# 05_-_QSPI_SD-CARD.net
KiCad netlist of a schematic drawn in Altium Designer
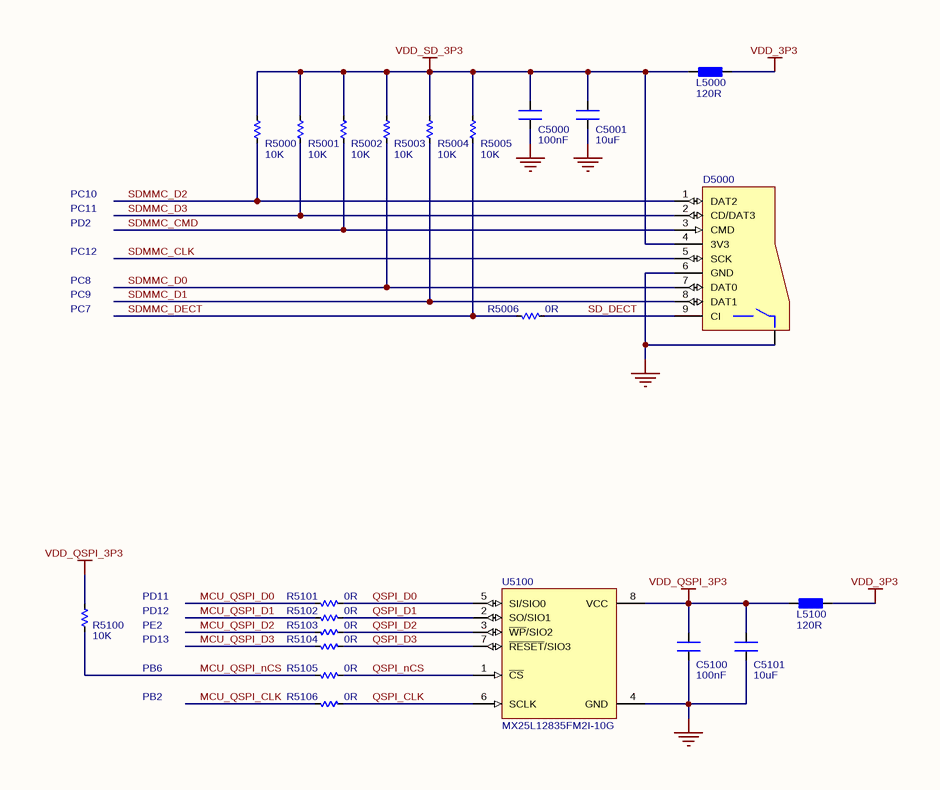
[diagram p0: 05 - QSPI & SD-CARD.SchDoc]

(export (version "E")
  (design (tool "Eeschema 10.0.6"))
  (components
    (comp (ref "C5000")
      (value "100nF")
      (footprint "CN-SMD-0402")
      (description "Ceramic Capacitor SMD 0402 100nF ±20% 16V")
      (fields (field (name "Comment") "Capacitor"))
      (libsource (lib "AS50") (part "Cap"))
    )
    (comp (ref "C5001")
      (value "10uF")
      (footprint "CN-SMD-0603")
      (description "Ceramic Capacitor SMD 0603 10uF ±20% 10V")
      (fields (field (name "Comment") "Capacitor"))
      (libsource (lib "AS50") (part "Cap"))
    )
    (comp (ref "C5100")
      (value "100nF")
      (footprint "CN-SMD-0402")
      (description "Ceramic Capacitor SMD 0402 100nF ±20% 16V")
      (fields (field (name "Comment") "Capacitor"))
      (libsource (lib "AS50") (part "Cap"))
    )
    (comp (ref "C5101")
      (value "10uF")
      (footprint "CN-SMD-0603")
      (description "Ceramic Capacitor SMD 0603 10uF ±20% 10V")
      (fields (field (name "Comment") "Capacitor"))
      (libsource (lib "AS50") (part "Cap"))
    )
    (comp (ref "D5000")
      (value "microSD card socket")
      (footprint "MICROSD1")
      (libsource (lib "AS50") (part "microSD card SDIO"))
    )
    (comp (ref "L5000")
      (value "120R")
      (footprint "L-SMD-0402")
      (description "Ferrite bead SMD 0402 120 Ohm @100MHz")
      (fields (field (name "Comment") "Ferrite bead"))
      (libsource (lib "AS50") (part "Ferrite bead"))
    )
    (comp (ref "L5100")
      (value "120R")
      (footprint "L-SMD-0402")
      (description "Ferrite bead SMD 0402 120 Ohm @100MHz")
      (fields (field (name "Comment") "Ferrite bead"))
      (libsource (lib "AS50") (part "Ferrite bead"))
    )
    (comp (ref "R5000")
      (value "10K")
      (footprint "RES-SMD-0402")
      (description "Resistor SMD 0402 10K 1% 0.063W")
      (fields (field (name "Comment") "Resistor"))
      (libsource (lib "AS50") (part "Res"))
    )
    (comp (ref "R5001")
      (value "10K")
      (footprint "RES-SMD-0402")
      (description "Resistor SMD 0402 10K 1% 0.063W")
      (fields (field (name "Comment") "Resistor"))
      (libsource (lib "AS50") (part "Res"))
    )
    (comp (ref "R5002")
      (value "10K")
      (footprint "RES-SMD-0402")
      (description "Resistor SMD 0402 10K 1% 0.063W")
      (fields (field (name "Comment") "Resistor"))
      (libsource (lib "AS50") (part "Res"))
    )
    (comp (ref "R5003")
      (value "10K")
      (footprint "RES-SMD-0402")
      (description "Resistor SMD 0402 10K 1% 0.063W")
      (fields (field (name "Comment") "Resistor"))
      (libsource (lib "AS50") (part "Res"))
    )
    (comp (ref "R5004")
      (value "10K")
      (footprint "RES-SMD-0402")
      (description "Resistor SMD 0402 10K 1% 0.063W")
      (fields (field (name "Comment") "Resistor"))
      (libsource (lib "AS50") (part "Res"))
    )
    (comp (ref "R5005")
      (value "10K")
      (footprint "RES-SMD-0402")
      (description "Resistor SMD 0402 10K 1% 0.063W")
      (fields (field (name "Comment") "Resistor"))
      (libsource (lib "AS50") (part "Res"))
    )
    (comp (ref "R5006")
      (value "0R")
      (footprint "RES-SMD-0402")
      (description "Resistor SMD 0402 0R 1% 0.063W")
      (fields (field (name "Comment") "Resistor"))
      (libsource (lib "AS50") (part "Res"))
    )
    (comp (ref "R5100")
      (value "10K")
      (footprint "RES-SMD-0402")
      (description "Resistor SMD 0402 10K 1% 0.063W")
      (fields (field (name "Comment") "Resistor"))
      (libsource (lib "AS50") (part "Res"))
    )
    (comp (ref "R5101")
      (value "0R")
      (footprint "RES-SMD-0402")
      (description "Resistor SMD 0402 0R 1% 0.063W")
      (fields (field (name "Comment") "Resistor"))
      (libsource (lib "AS50") (part "Res"))
    )
    (comp (ref "R5102")
      (value "0R")
      (footprint "RES-SMD-0402")
      (description "Resistor SMD 0402 0R 1% 0.063W")
      (fields (field (name "Comment") "Resistor"))
      (libsource (lib "AS50") (part "Res"))
    )
    (comp (ref "R5103")
      (value "0R")
      (footprint "RES-SMD-0402")
      (description "Resistor SMD 0402 0R 1% 0.063W")
      (fields (field (name "Comment") "Resistor"))
      (libsource (lib "AS50") (part "Res"))
    )
    (comp (ref "R5104")
      (value "0R")
      (footprint "RES-SMD-0402")
      (description "Resistor SMD 0402 0R 1% 0.063W")
      (fields (field (name "Comment") "Resistor"))
      (libsource (lib "AS50") (part "Res"))
    )
    (comp (ref "R5105")
      (value "0R")
      (footprint "RES-SMD-0402")
      (description "Resistor SMD 0402 0R 1% 0.063W")
      (fields (field (name "Comment") "Resistor"))
      (libsource (lib "AS50") (part "Res"))
    )
    (comp (ref "R5106")
      (value "0R")
      (footprint "RES-SMD-0402")
      (description "Resistor SMD 0402 0R 1% 0.063W")
      (fields (field (name "Comment") "Resistor"))
      (libsource (lib "AS50") (part "Res"))
    )
    (comp (ref "U5100")
      (value "MX25L12835FM2I-10G")
      (footprint "SOIC127P798X216-8N")
      (description "Macronix 3V, 128M-BIT [x1/x2/x4] CMOS MXSMIO® (Serial Multi I/O) Flash Memory")
      (libsource (lib "AS50") (part "MX25L12835FM2I-10G"))
    )
  )
  (nets
    (net (code "1") (name "/MCU_QSPI_CLK") (class "Default")
      (node (ref "R5106") (pin "2") (pinfunction "2_2") (pintype "passive"))
    )
    (net (code "2") (name "/MCU_QSPI_D0") (class "Default")
      (node (ref "R5101") (pin "2") (pinfunction "2_2") (pintype "passive"))
    )
    (net (code "3") (name "/MCU_QSPI_D1") (class "Default")
      (node (ref "R5102") (pin "2") (pinfunction "2_2") (pintype "passive"))
    )
    (net (code "4") (name "/MCU_QSPI_D2") (class "Default")
      (node (ref "R5103") (pin "2") (pinfunction "2_2") (pintype "passive"))
    )
    (net (code "5") (name "/MCU_QSPI_D3") (class "Default")
      (node (ref "R5104") (pin "2") (pinfunction "2_2") (pintype "passive"))
    )
    (net (code "6") (name "/MCU_QSPI_nCS") (class "Default")
      (node (ref "R5100") (pin "2") (pinfunction "2_2") (pintype "passive"))
      (node (ref "R5105") (pin "2") (pinfunction "2_2") (pintype "passive"))
    )
    (net (code "7") (name "/QSPI_CLK") (class "Default")
      (node (ref "R5106") (pin "1") (pinfunction "1_1") (pintype "passive"))
      (node (ref "U5100") (pin "6") (pinfunction "SCLK_6") (pintype "input"))
    )
    (net (code "8") (name "/QSPI_D0") (class "Default")
      (node (ref "R5101") (pin "1") (pinfunction "1_1") (pintype "passive"))
      (node (ref "U5100") (pin "5") (pinfunction "SI/SIO0_5") (pintype "bidirectional"))
    )
    (net (code "9") (name "/QSPI_D1") (class "Default")
      (node (ref "R5102") (pin "1") (pinfunction "1_1") (pintype "passive"))
      (node (ref "U5100") (pin "2") (pinfunction "SO/SIO1_2") (pintype "bidirectional"))
    )
    (net (code "10") (name "/QSPI_D2") (class "Default")
      (node (ref "R5103") (pin "1") (pinfunction "1_1") (pintype "passive"))
      (node (ref "U5100") (pin "3") (pinfunction "~{WP}/SIO2_3") (pintype "bidirectional"))
    )
    (net (code "11") (name "/QSPI_D3") (class "Default")
      (node (ref "R5104") (pin "1") (pinfunction "1_1") (pintype "passive"))
      (node (ref "U5100") (pin "7") (pinfunction "~{RESET}/SIO3_7") (pintype "bidirectional"))
    )
    (net (code "12") (name "/QSPI_nCS") (class "Default")
      (node (ref "R5105") (pin "1") (pinfunction "1_1") (pintype "passive"))
      (node (ref "U5100") (pin "1") (pinfunction "~{CS}_1") (pintype "input"))
    )
    (net (code "13") (name "/SDMMC_CLK") (class "Default")
      (node (ref "D5000") (pin "5") (pinfunction "SCK_5") (pintype "bidirectional"))
    )
    (net (code "14") (name "/SDMMC_CMD") (class "Default")
      (node (ref "D5000") (pin "3") (pinfunction "CMD_3") (pintype "input"))
      (node (ref "R5002") (pin "2") (pinfunction "2_2") (pintype "passive"))
    )
    (net (code "15") (name "/SDMMC_D0") (class "Default")
      (node (ref "D5000") (pin "7") (pinfunction "DAT0_7") (pintype "bidirectional"))
      (node (ref "R5003") (pin "2") (pinfunction "2_2") (pintype "passive"))
    )
    (net (code "16") (name "/SDMMC_D1") (class "Default")
      (node (ref "D5000") (pin "8") (pinfunction "DAT1_8") (pintype "bidirectional"))
      (node (ref "R5004") (pin "2") (pinfunction "2_2") (pintype "passive"))
    )
    (net (code "17") (name "/SDMMC_D2") (class "Default")
      (node (ref "D5000") (pin "1") (pinfunction "DAT2_1") (pintype "bidirectional"))
      (node (ref "R5000") (pin "2") (pinfunction "2_2") (pintype "passive"))
    )
    (net (code "18") (name "/SDMMC_D3") (class "Default")
      (node (ref "D5000") (pin "2") (pinfunction "CD/DAT3_2") (pintype "bidirectional"))
      (node (ref "R5001") (pin "2") (pinfunction "2_2") (pintype "passive"))
    )
    (net (code "19") (name "/SDMMC_DECT") (class "Default")
      (node (ref "R5005") (pin "2") (pinfunction "2_2") (pintype "passive"))
      (node (ref "R5006") (pin "2") (pinfunction "2_2") (pintype "passive"))
    )
    (net (code "20") (name "/SD_DECT") (class "Default")
      (node (ref "D5000") (pin "9") (pinfunction "CI_9") (pintype "passive"))
      (node (ref "R5006") (pin "1") (pinfunction "1_1") (pintype "passive"))
    )
    (net (code "21") (name "GND") (class "Default")
      (node (ref "C5000") (pin "1") (pinfunction "1_1") (pintype "passive"))
      (node (ref "C5001") (pin "1") (pinfunction "1_1") (pintype "passive"))
      (node (ref "C5100") (pin "1") (pinfunction "1_1") (pintype "passive"))
      (node (ref "C5101") (pin "1") (pinfunction "1_1") (pintype "passive"))
      (node (ref "D5000") (pin "0") (pinfunction "NC_0") (pintype "passive"))
      (node (ref "D5000") (pin "6") (pinfunction "GND_6") (pintype "power_in"))
      (node (ref "U5100") (pin "4") (pinfunction "GND_4") (pintype "power_in"))
    )
    (net (code "22") (name "VDD_3P3") (class "Default")
      (node (ref "L5000") (pin "1") (pinfunction "1_1") (pintype "passive"))
      (node (ref "L5100") (pin "1") (pinfunction "1_1") (pintype "passive"))
    )
    (net (code "23") (name "VDD_QSPI_3P3") (class "Default")
      (node (ref "C5100") (pin "2") (pinfunction "2_2") (pintype "passive"))
      (node (ref "C5101") (pin "2") (pinfunction "2_2") (pintype "passive"))
      (node (ref "L5100") (pin "2") (pinfunction "2_2") (pintype "passive"))
      (node (ref "R5100") (pin "1") (pinfunction "1_1") (pintype "passive"))
      (node (ref "U5100") (pin "8") (pinfunction "VCC_8") (pintype "power_in"))
    )
    (net (code "24") (name "VDD_SD_3P3") (class "Default")
      (node (ref "C5000") (pin "2") (pinfunction "2_2") (pintype "passive"))
      (node (ref "C5001") (pin "2") (pinfunction "2_2") (pintype "passive"))
      (node (ref "D5000") (pin "4") (pinfunction "3V3_4") (pintype "power_in"))
      (node (ref "L5000") (pin "2") (pinfunction "2_2") (pintype "passive"))
      (node (ref "R5000") (pin "1") (pinfunction "1_1") (pintype "passive"))
      (node (ref "R5001") (pin "1") (pinfunction "1_1") (pintype "passive"))
      (node (ref "R5002") (pin "1") (pinfunction "1_1") (pintype "passive"))
      (node (ref "R5003") (pin "1") (pinfunction "1_1") (pintype "passive"))
      (node (ref "R5004") (pin "1") (pinfunction "1_1") (pintype "passive"))
      (node (ref "R5005") (pin "1") (pinfunction "1_1") (pintype "passive"))
    )
  )
)
